# Encoder.net
KiCad netlist of a schematic drawn in EAGLE
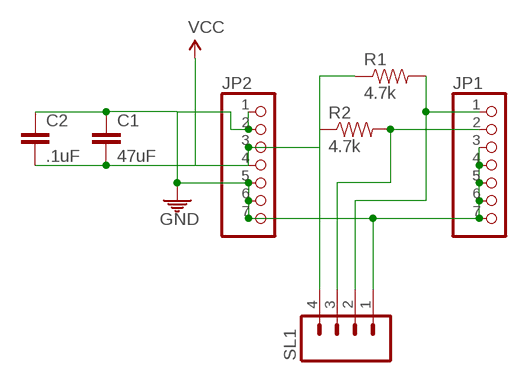
[diagram p0: schematic, sheet 1]

(export (version "E")
  (design (tool "Eeschema 10.0.6"))
  (components
    (comp (ref "C1")
      (value "47uF")
      (footprint "eagle-import:0805")
      (libsource (lib "eagle-import") (part "CAP0805"))
    )
    (comp (ref "C2")
      (value ".1uF")
      (footprint "eagle-import:0805")
      (libsource (lib "eagle-import") (part "CAP0805"))
    )
    (comp (ref "JP1")
      (value "PINHD-1X7")
      (footprint "eagle-import:1X07")
      (libsource (lib "eagle-import") (part "PINHD-1X7"))
    )
    (comp (ref "JP2")
      (value "PINHD-1X7")
      (footprint "eagle-import:1X07")
      (libsource (lib "eagle-import") (part "PINHD-1X7"))
    )
    (comp (ref "R1")
      (value "4.7k")
      (footprint "eagle-import:0805")
      (libsource (lib "eagle-import") (part "RESISTOR0805-RES"))
    )
    (comp (ref "R2")
      (value "4.7k")
      (footprint "eagle-import:0805")
      (libsource (lib "eagle-import") (part "RESISTOR0805-RES"))
    )
    (comp (ref "SL1")
      (value "M04LOCK")
      (footprint "eagle-import:1X04_LOCK")
      (libsource (lib "eagle-import") (part "M04LOCK"))
    )
  )
  (nets
    (net (code "1") (name "GND") (class "Default")
      (node (ref "C1") (pin "1") (pinfunction "1_1") (pintype "passive"))
      (node (ref "C2") (pin "1") (pinfunction "1_1") (pintype "passive"))
      (node (ref "JP1") (pin "3") (pinfunction "3_3") (pintype "passive"))
      (node (ref "JP1") (pin "4") (pinfunction "4_4") (pintype "passive"))
      (node (ref "JP1") (pin "5") (pinfunction "5_5") (pintype "passive"))
      (node (ref "JP1") (pin "6") (pinfunction "6_6") (pintype "passive"))
      (node (ref "JP1") (pin "7") (pinfunction "7_7") (pintype "passive"))
      (node (ref "JP2") (pin "1") (pinfunction "1_1") (pintype "passive"))
      (node (ref "JP2") (pin "2") (pinfunction "2_2") (pintype "passive"))
      (node (ref "JP2") (pin "5") (pinfunction "5_5") (pintype "passive"))
      (node (ref "JP2") (pin "6") (pinfunction "6_6") (pintype "passive"))
      (node (ref "JP2") (pin "7") (pinfunction "7_7") (pintype "passive"))
      (node (ref "SL1") (pin "1") (pinfunction "1_1") (pintype "passive"))
    )
    (net (code "2") (name "Net-(JP1-Pad1)") (class "Default")
      (node (ref "JP1") (pin "1") (pinfunction "1_1") (pintype "passive"))
      (node (ref "R1") (pin "2") (pinfunction "2_2") (pintype "passive"))
      (node (ref "SL1") (pin "2") (pinfunction "2_2") (pintype "passive"))
    )
    (net (code "3") (name "Net-(JP1-Pad2)") (class "Default")
      (node (ref "JP1") (pin "2") (pinfunction "2_2") (pintype "passive"))
      (node (ref "R2") (pin "2") (pinfunction "2_2") (pintype "passive"))
      (node (ref "SL1") (pin "3") (pinfunction "3_3") (pintype "passive"))
    )
    (net (code "4") (name "VCC") (class "Default")
      (node (ref "C1") (pin "2") (pinfunction "2_2") (pintype "passive"))
      (node (ref "C2") (pin "2") (pinfunction "2_2") (pintype "passive"))
      (node (ref "JP2") (pin "3") (pinfunction "3_3") (pintype "passive"))
      (node (ref "JP2") (pin "4") (pinfunction "4_4") (pintype "passive"))
      (node (ref "R1") (pin "1") (pinfunction "1_1") (pintype "passive"))
      (node (ref "R2") (pin "1") (pinfunction "1_1") (pintype "passive"))
      (node (ref "SL1") (pin "4") (pinfunction "4_4") (pintype "passive"))
    )
  )
)
